# tictactoe19_11.net
KiCad netlist of a schematic drawn in EAGLE
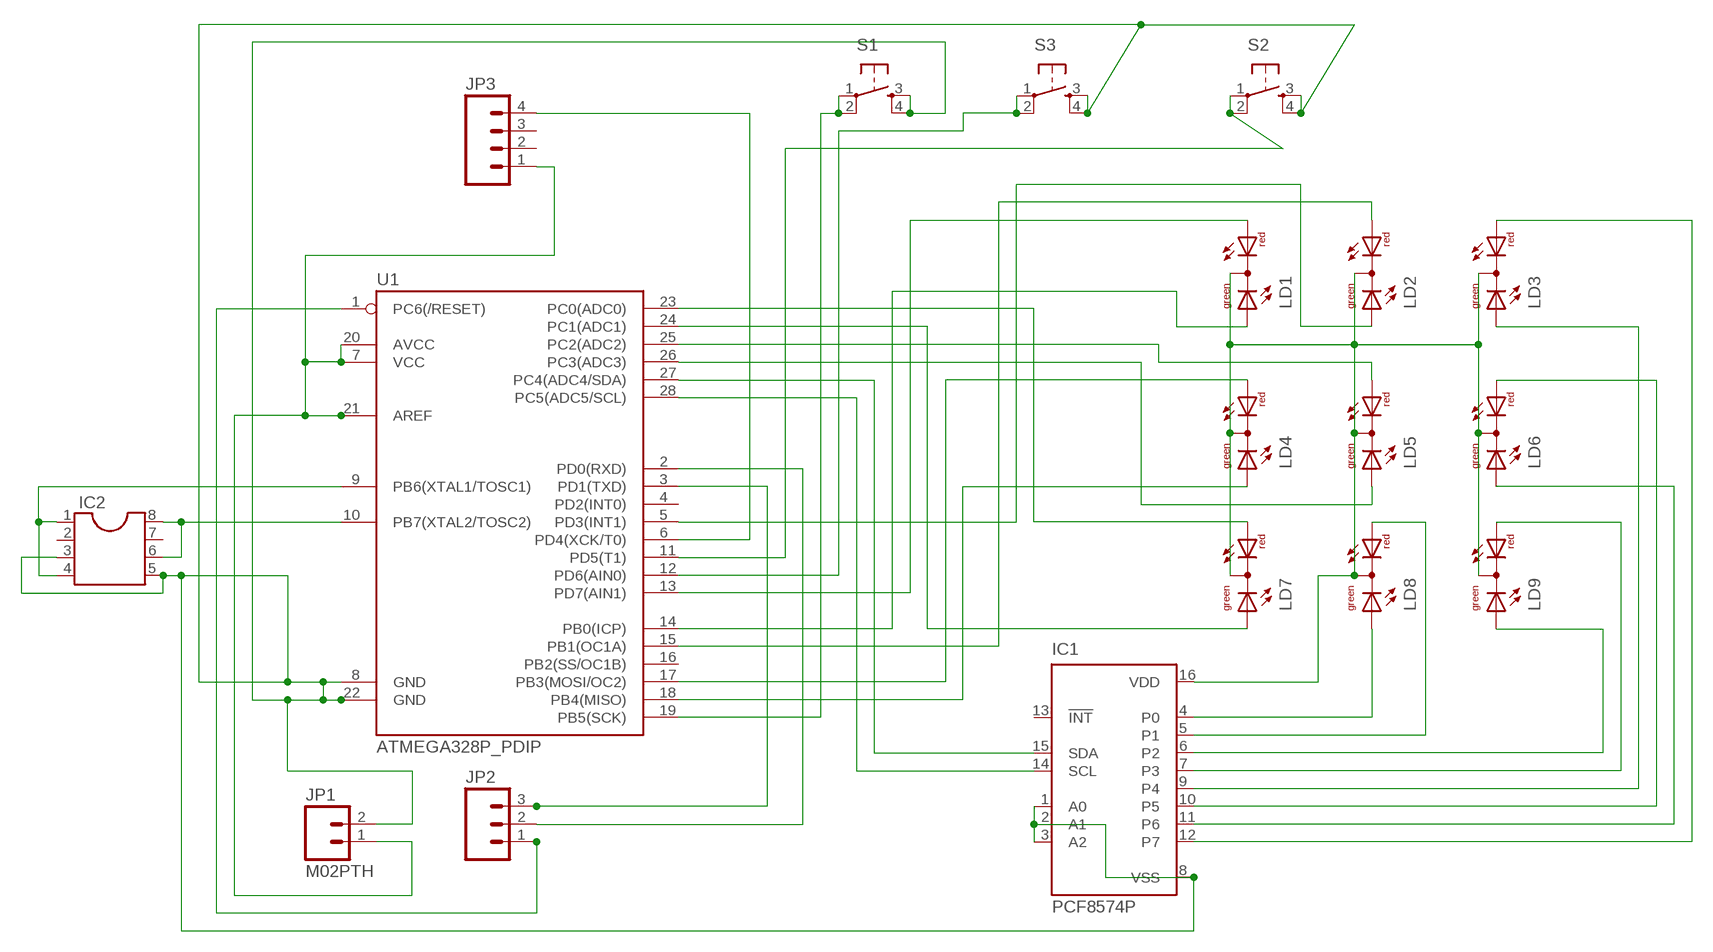
[diagram p0: schematic, sheet 1]

(export (version "E")
  (design (tool "Eeschema 10.0.6"))
  (components
    (comp (ref "IC1")
      (value "PCF8574P")
      (footprint "eagle-import:DIL16")
      (fields (field (name "MPN") "PCF8574PN"))
      (libsource (lib "eagle-import") (part "PCF8574P"))
    )
    (comp (ref "IC2")
      (value "DIL8S")
      (footprint "eagle-import:SOCKET-08")
      (libsource (lib "eagle-import") (part "DIL8S"))
    )
    (comp (ref "JP1")
      (value "M02PTH")
      (footprint "eagle-import:1X02")
      (libsource (lib "eagle-import") (part "M02PTH"))
    )
    (comp (ref "JP2")
      (value "M03PTH")
      (footprint "eagle-import:1X03")
      (libsource (lib "eagle-import") (part "M03PTH"))
    )
    (comp (ref "JP3")
      (value "M04PTH")
      (footprint "eagle-import:1X04")
      (libsource (lib "eagle-import") (part "M04PTH"))
    )
    (comp (ref "LD1")
      (value "DUOLED-RG-C")
      (footprint "eagle-import:DUOLED-C-5MM")
      (libsource (lib "eagle-import") (part "DUOLED-RG-C"))
    )
    (comp (ref "LD2")
      (value "DUOLED-RG-C")
      (footprint "eagle-import:DUOLED-C-5MM")
      (libsource (lib "eagle-import") (part "DUOLED-RG-C"))
    )
    (comp (ref "LD3")
      (value "DUOLED-RG-C")
      (footprint "eagle-import:DUOLED-C-5MM")
      (libsource (lib "eagle-import") (part "DUOLED-RG-C"))
    )
    (comp (ref "LD4")
      (value "DUOLED-RG-C")
      (footprint "eagle-import:DUOLED-C-5MM")
      (libsource (lib "eagle-import") (part "DUOLED-RG-C"))
    )
    (comp (ref "LD5")
      (value "DUOLED-RG-C")
      (footprint "eagle-import:DUOLED-C-5MM")
      (libsource (lib "eagle-import") (part "DUOLED-RG-C"))
    )
    (comp (ref "LD6")
      (value "DUOLED-RG-C")
      (footprint "eagle-import:DUOLED-C-5MM")
      (libsource (lib "eagle-import") (part "DUOLED-RG-C"))
    )
    (comp (ref "LD7")
      (value "DUOLED-RG-C")
      (footprint "eagle-import:DUOLED-C-5MM")
      (libsource (lib "eagle-import") (part "DUOLED-RG-C"))
    )
    (comp (ref "LD8")
      (value "DUOLED-RG-C")
      (footprint "eagle-import:DUOLED-C-5MM")
      (libsource (lib "eagle-import") (part "DUOLED-RG-C"))
    )
    (comp (ref "LD9")
      (value "DUOLED-RG-C")
      (footprint "eagle-import:DUOLED-C-5MM")
      (libsource (lib "eagle-import") (part "DUOLED-RG-C"))
    )
    (comp (ref "S1")
      (value "TAC_SWITCHPTH")
      (footprint "eagle-import:TACTILE-PTH")
      (libsource (lib "eagle-import") (part "TAC_SWITCHPTH"))
    )
    (comp (ref "S2")
      (value "TAC_SWITCHPTH")
      (footprint "eagle-import:TACTILE-PTH")
      (libsource (lib "eagle-import") (part "TAC_SWITCHPTH"))
    )
    (comp (ref "S3")
      (value "TAC_SWITCHPTH")
      (footprint "eagle-import:TACTILE-PTH")
      (libsource (lib "eagle-import") (part "TAC_SWITCHPTH"))
    )
    (comp (ref "U1")
      (value "ATMEGA328P_PDIP")
      (footprint "eagle-import:DIL28-3")
      (libsource (lib "eagle-import") (part "ATMEGA328P_PDIP"))
    )
  )
  (nets
    (net (code "1") (name "/VCC") (class "Default")
      (node (ref "IC1") (pin "16") (pinfunction "VDD_16") (pintype "power_in"))
      (node (ref "JP1") (pin "1") (pinfunction "1_1") (pintype "passive"))
      (node (ref "JP3") (pin "1") (pinfunction "1_1") (pintype "passive"))
      (node (ref "LD1") (pin "C") (pinfunction "C_C") (pintype "passive"))
      (node (ref "LD2") (pin "C") (pinfunction "C_C") (pintype "passive"))
      (node (ref "LD3") (pin "C") (pinfunction "C_C") (pintype "passive"))
      (node (ref "LD4") (pin "C") (pinfunction "C_C") (pintype "passive"))
      (node (ref "LD5") (pin "C") (pinfunction "C_C") (pintype "passive"))
      (node (ref "LD6") (pin "C") (pinfunction "C_C") (pintype "passive"))
      (node (ref "LD7") (pin "C") (pinfunction "C_C") (pintype "passive"))
      (node (ref "LD8") (pin "C") (pinfunction "C_C") (pintype "passive"))
      (node (ref "LD9") (pin "C") (pinfunction "C_C") (pintype "passive"))
      (node (ref "U1") (pin "20") (pinfunction "AVCC_20") (pintype "bidirectional"))
      (node (ref "U1") (pin "21") (pinfunction "AREF_21") (pintype "bidirectional"))
      (node (ref "U1") (pin "7") (pinfunction "VCC_7") (pintype "bidirectional"))
    )
    (net (code "2") (name "Net-(IC1-A0)") (class "Default")
      (node (ref "IC1") (pin "1") (pinfunction "A0_1") (pintype "input"))
      (node (ref "IC1") (pin "2") (pinfunction "A1_2") (pintype "input"))
      (node (ref "IC1") (pin "3") (pinfunction "A2_3") (pintype "input"))
      (node (ref "IC1") (pin "8") (pinfunction "VSS_8") (pintype "power_in"))
      (node (ref "IC2") (pin "3") (pinfunction "3_3") (pintype "passive"))
      (node (ref "IC2") (pin "5") (pinfunction "5_5") (pintype "passive"))
      (node (ref "JP1") (pin "2") (pinfunction "2_2") (pintype "passive"))
      (node (ref "S1") (pin "3") (pinfunction "3_3") (pintype "passive"))
      (node (ref "S1") (pin "4") (pinfunction "4_4") (pintype "passive"))
      (node (ref "S2") (pin "3") (pinfunction "3_3") (pintype "passive"))
      (node (ref "S2") (pin "4") (pinfunction "4_4") (pintype "passive"))
      (node (ref "S3") (pin "3") (pinfunction "3_3") (pintype "passive"))
      (node (ref "S3") (pin "4") (pinfunction "4_4") (pintype "passive"))
      (node (ref "U1") (pin "22") (pinfunction "GND_22") (pintype "bidirectional"))
      (node (ref "U1") (pin "8") (pinfunction "GND_8") (pintype "bidirectional"))
    )
    (net (code "3") (name "Net-(IC1-P0)") (class "Default")
      (node (ref "IC1") (pin "4") (pinfunction "P0_4") (pintype "bidirectional"))
      (node (ref "LD8") (pin "AX") (pinfunction "AG_AX") (pintype "passive"))
    )
    (net (code "4") (name "Net-(IC1-P1)") (class "Default")
      (node (ref "IC1") (pin "5") (pinfunction "P1_5") (pintype "bidirectional"))
      (node (ref "LD8") (pin "AR") (pinfunction "AR_AR") (pintype "passive"))
    )
    (net (code "5") (name "Net-(IC1-P2)") (class "Default")
      (node (ref "IC1") (pin "6") (pinfunction "P2_6") (pintype "bidirectional"))
      (node (ref "LD9") (pin "AX") (pinfunction "AG_AX") (pintype "passive"))
    )
    (net (code "6") (name "Net-(IC1-P3)") (class "Default")
      (node (ref "IC1") (pin "7") (pinfunction "P3_7") (pintype "bidirectional"))
      (node (ref "LD9") (pin "AR") (pinfunction "AR_AR") (pintype "passive"))
    )
    (net (code "7") (name "Net-(IC1-P4)") (class "Default")
      (node (ref "IC1") (pin "9") (pinfunction "P4_9") (pintype "bidirectional"))
      (node (ref "LD3") (pin "AX") (pinfunction "AG_AX") (pintype "passive"))
    )
    (net (code "8") (name "Net-(IC1-P5)") (class "Default")
      (node (ref "IC1") (pin "10") (pinfunction "P5_10") (pintype "bidirectional"))
      (node (ref "LD6") (pin "AR") (pinfunction "AR_AR") (pintype "passive"))
    )
    (net (code "9") (name "Net-(IC1-P6)") (class "Default")
      (node (ref "IC1") (pin "11") (pinfunction "P6_11") (pintype "bidirectional"))
      (node (ref "LD6") (pin "AX") (pinfunction "AG_AX") (pintype "passive"))
    )
    (net (code "10") (name "Net-(IC1-P7)") (class "Default")
      (node (ref "IC1") (pin "12") (pinfunction "P7_12") (pintype "bidirectional"))
      (node (ref "LD3") (pin "AR") (pinfunction "AR_AR") (pintype "passive"))
    )
    (net (code "11") (name "Net-(IC1-SCL)") (class "Default")
      (node (ref "IC1") (pin "14") (pinfunction "SCL_14") (pintype "input"))
      (node (ref "U1") (pin "28") (pinfunction "PC5(ADC5/SCL)_28") (pintype "bidirectional"))
    )
    (net (code "12") (name "Net-(IC1-SDA)") (class "Default")
      (node (ref "IC1") (pin "15") (pinfunction "SDA_15") (pintype "bidirectional"))
      (node (ref "U1") (pin "27") (pinfunction "PC4(ADC4/SDA)_27") (pintype "bidirectional"))
    )
    (net (code "13") (name "Net-(LD1-AG)") (class "Default")
      (node (ref "LD1") (pin "AX") (pinfunction "AG_AX") (pintype "passive"))
      (node (ref "U1") (pin "14") (pinfunction "PB0(ICP)_14") (pintype "bidirectional"))
    )
    (net (code "14") (name "Net-(LD2-AG)") (class "Default")
      (node (ref "LD2") (pin "AX") (pinfunction "AG_AX") (pintype "passive"))
      (node (ref "U1") (pin "5") (pinfunction "PD3(INT1)_5") (pintype "bidirectional"))
    )
    (net (code "15") (name "Net-(LD4-AG)") (class "Default")
      (node (ref "LD4") (pin "AX") (pinfunction "AG_AX") (pintype "passive"))
      (node (ref "U1") (pin "18") (pinfunction "PB4(MISO)_18") (pintype "bidirectional"))
    )
    (net (code "16") (name "Net-(LD5-AG)") (class "Default")
      (node (ref "LD5") (pin "AX") (pinfunction "AG_AX") (pintype "passive"))
      (node (ref "U1") (pin "26") (pinfunction "PC3(ADC3)_26") (pintype "bidirectional"))
    )
    (net (code "17") (name "Net-(LD7-AG)") (class "Default")
      (node (ref "LD7") (pin "AX") (pinfunction "AG_AX") (pintype "passive"))
      (node (ref "U1") (pin "24") (pinfunction "PC1(ADC1)_24") (pintype "bidirectional"))
    )
    (net (code "18") (name "Net-(U1-PB1(OC1A))") (class "Default")
      (node (ref "LD2") (pin "AR") (pinfunction "AR_AR") (pintype "passive"))
      (node (ref "U1") (pin "15") (pinfunction "PB1(OC1A)_15") (pintype "bidirectional"))
    )
    (net (code "19") (name "Net-(U1-PB3(MOSI{slash}OC2))") (class "Default")
      (node (ref "LD4") (pin "AR") (pinfunction "AR_AR") (pintype "passive"))
      (node (ref "U1") (pin "17") (pinfunction "PB3(MOSI/OC2)_17") (pintype "bidirectional"))
    )
    (net (code "20") (name "Net-(U1-PB5(SCK))") (class "Default")
      (node (ref "S1") (pin "1") (pinfunction "1_1") (pintype "passive"))
      (node (ref "S1") (pin "2") (pinfunction "2_2") (pintype "passive"))
      (node (ref "U1") (pin "19") (pinfunction "PB5(SCK)_19") (pintype "bidirectional"))
    )
    (net (code "21") (name "Net-(U1-PB6(XTAL1{slash}TOSC1))") (class "Default")
      (node (ref "IC2") (pin "1") (pinfunction "1_1") (pintype "passive"))
      (node (ref "IC2") (pin "4") (pinfunction "4_4") (pintype "passive"))
      (node (ref "U1") (pin "9") (pinfunction "PB6(XTAL1/TOSC1)_9") (pintype "bidirectional"))
    )
    (net (code "22") (name "Net-(U1-PB7(XTAL2{slash}TOSC2))") (class "Default")
      (node (ref "IC2") (pin "6") (pinfunction "6_6") (pintype "passive"))
      (node (ref "IC2") (pin "8") (pinfunction "8_8") (pintype "passive"))
      (node (ref "U1") (pin "10") (pinfunction "PB7(XTAL2/TOSC2)_10") (pintype "bidirectional"))
    )
    (net (code "23") (name "Net-(U1-PC0(ADC0))") (class "Default")
      (node (ref "LD7") (pin "AR") (pinfunction "AR_AR") (pintype "passive"))
      (node (ref "U1") (pin "23") (pinfunction "PC0(ADC0)_23") (pintype "bidirectional"))
    )
    (net (code "24") (name "Net-(U1-PC2(ADC2))") (class "Default")
      (node (ref "LD5") (pin "AR") (pinfunction "AR_AR") (pintype "passive"))
      (node (ref "U1") (pin "25") (pinfunction "PC2(ADC2)_25") (pintype "bidirectional"))
    )
    (net (code "25") (name "Net-(U1-PC6({slash}RESET))") (class "Default")
      (node (ref "JP2") (pin "1") (pinfunction "1_1") (pintype "passive"))
      (node (ref "U1") (pin "1") (pinfunction "PC6(/RESET)_1") (pintype "bidirectional"))
    )
    (net (code "26") (name "Net-(U1-PD0(RXD))") (class "Default")
      (node (ref "JP2") (pin "2") (pinfunction "2_2") (pintype "passive"))
      (node (ref "U1") (pin "2") (pinfunction "PD0(RXD)_2") (pintype "bidirectional"))
    )
    (net (code "27") (name "Net-(U1-PD1(TXD))") (class "Default")
      (node (ref "JP2") (pin "3") (pinfunction "3_3") (pintype "passive"))
      (node (ref "U1") (pin "3") (pinfunction "PD1(TXD)_3") (pintype "bidirectional"))
    )
    (net (code "28") (name "Net-(U1-PD4(XCK{slash}T0))") (class "Default")
      (node (ref "JP3") (pin "4") (pinfunction "4_4") (pintype "passive"))
      (node (ref "U1") (pin "6") (pinfunction "PD4(XCK/T0)_6") (pintype "bidirectional"))
    )
    (net (code "29") (name "Net-(U1-PD5(T1))") (class "Default")
      (node (ref "S2") (pin "1") (pinfunction "1_1") (pintype "passive"))
      (node (ref "S2") (pin "2") (pinfunction "2_2") (pintype "passive"))
      (node (ref "U1") (pin "11") (pinfunction "PD5(T1)_11") (pintype "bidirectional"))
    )
    (net (code "30") (name "Net-(U1-PD6(AIN0))") (class "Default")
      (node (ref "S3") (pin "1") (pinfunction "1_1") (pintype "passive"))
      (node (ref "S3") (pin "2") (pinfunction "2_2") (pintype "passive"))
      (node (ref "U1") (pin "12") (pinfunction "PD6(AIN0)_12") (pintype "bidirectional"))
    )
    (net (code "31") (name "Net-(U1-PD7(AIN1))") (class "Default")
      (node (ref "LD1") (pin "AR") (pinfunction "AR_AR") (pintype "passive"))
      (node (ref "U1") (pin "13") (pinfunction "PD7(AIN1)_13") (pintype "bidirectional"))
    )
    (net (code "32") (name "unconnected-(IC1-~{INT}-Pad13)") (class "Default")
      (node (ref "IC1") (pin "13") (pinfunction "~{INT}_13") (pintype "output"))
    )
    (net (code "33") (name "unconnected-(IC2-Pad2)") (class "Default")
      (node (ref "IC2") (pin "2") (pinfunction "2_2") (pintype "passive"))
    )
    (net (code "34") (name "unconnected-(IC2-Pad7)") (class "Default")
      (node (ref "IC2") (pin "7") (pinfunction "7_7") (pintype "passive"))
    )
    (net (code "35") (name "unconnected-(JP3-Pad2)") (class "Default")
      (node (ref "JP3") (pin "2") (pinfunction "2_2") (pintype "passive"))
    )
    (net (code "36") (name "unconnected-(JP3-Pad3)") (class "Default")
      (node (ref "JP3") (pin "3") (pinfunction "3_3") (pintype "passive"))
    )
    (net (code "37") (name "unconnected-(U1-PB2(SS{slash}OC1B)-Pad16)") (class "Default")
      (node (ref "U1") (pin "16") (pinfunction "PB2(SS/OC1B)_16") (pintype "bidirectional"))
    )
    (net (code "38") (name "unconnected-(U1-PD2(INT0)-Pad4)") (class "Default")
      (node (ref "U1") (pin "4") (pinfunction "PD2(INT0)_4") (pintype "bidirectional"))
    )
  )
)
